# SnapItBreakoutRev1.net
KiCad netlist of a schematic drawn in Altium Designer
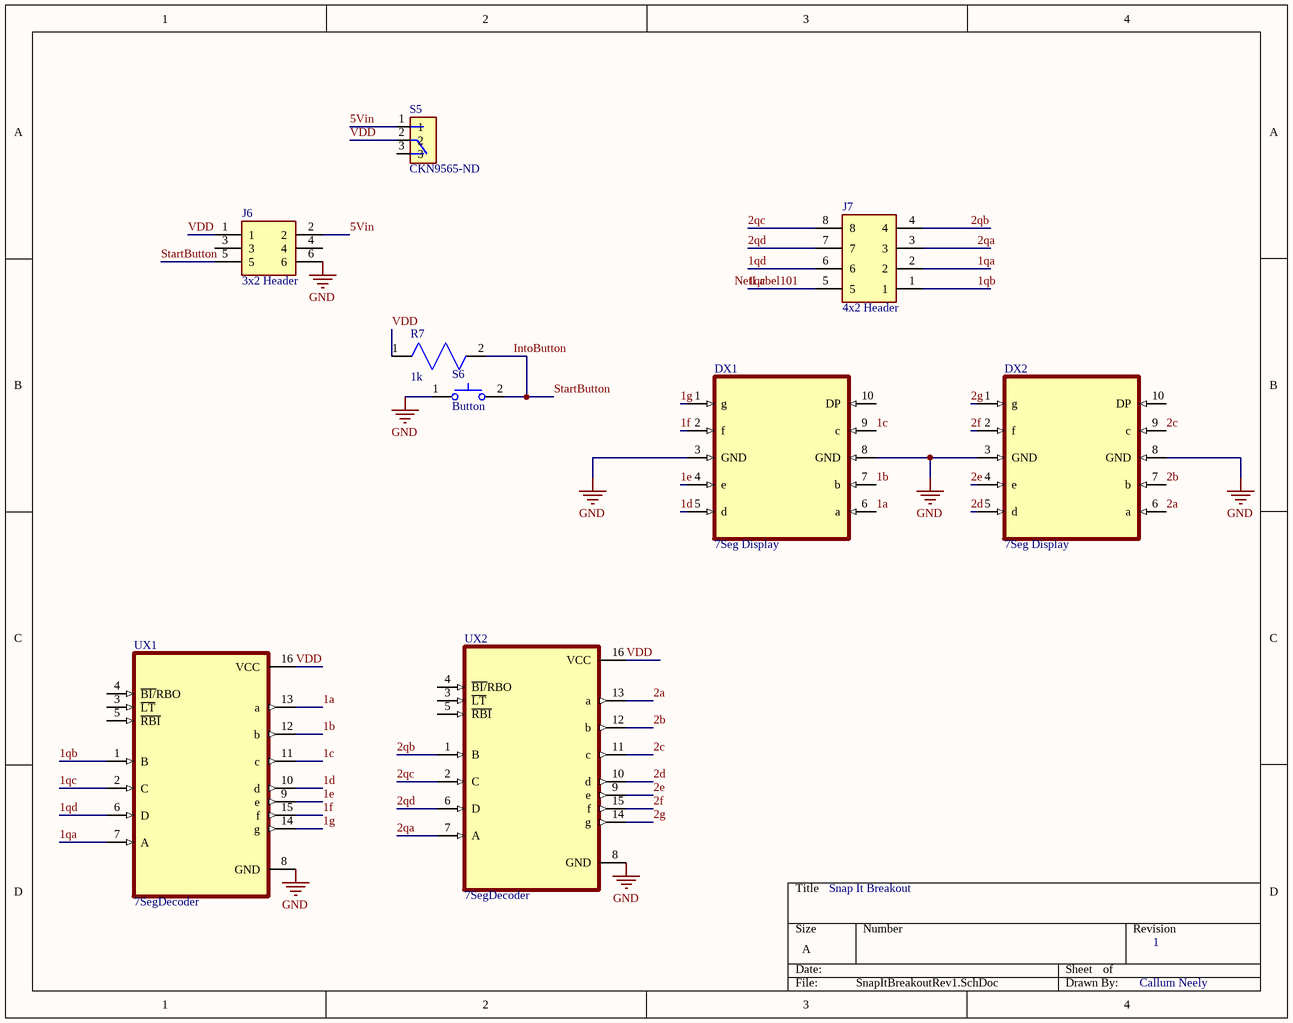
[diagram p0: SnapItBreakoutRev1.SchDoc]

(export (version "E")
  (design (tool "Eeschema 10.0.6"))
  (components
    (comp (ref "DX1")
      (value "7Seg Display")
      (footprint "7 Seg")
      (libsource (lib "JDLib") (part "7Seg Display"))
    )
    (comp (ref "DX2")
      (value "7Seg Display")
      (footprint "7 Seg")
      (libsource (lib "JDLib") (part "7Seg Display"))
    )
    (comp (ref "J6")
      (value "3x2 Header")
      (footprint "3x2 Header")
      (libsource (lib "JDLib") (part "3x2 Header"))
    )
    (comp (ref "J7")
      (value "4x2 Header")
      (footprint "4x2 Header")
      (libsource (lib "JDLib") (part "4x2 Header"))
    )
    (comp (ref "R7") (value "1k") (footprint "0402Basic") (libsource (lib "JDLib") (part "RES")))
    (comp (ref "S5")
      (value "CKN9565-ND")
      (footprint "Slide Switch")
      (libsource (lib "JDLib") (part "Switch"))
    )
    (comp (ref "S6") (value "Button") (footprint "Pushbutton") (libsource (lib "JDLib") (part "Button")))
    (comp (ref "UX1")
      (value "7SegDecoder")
      (footprint "DisplayDecoder")
      (libsource (lib "JDLib") (part "7SegDecoder"))
    )
    (comp (ref "UX2")
      (value "7SegDecoder")
      (footprint "DisplayDecoder")
      (libsource (lib "JDLib") (part "7SegDecoder"))
    )
  )
  (nets
    (net (code "1") (name "/1a") (class "Default")
      (node (ref "DX1") (pin "6") (pinfunction "a_6") (pintype "input"))
      (node (ref "UX1") (pin "13") (pinfunction "a_13") (pintype "output"))
    )
    (net (code "2") (name "/1b") (class "Default")
      (node (ref "DX1") (pin "7") (pinfunction "b_7") (pintype "input"))
      (node (ref "UX1") (pin "12") (pinfunction "b_12") (pintype "output"))
    )
    (net (code "3") (name "/1c") (class "Default")
      (node (ref "DX1") (pin "9") (pinfunction "c_9") (pintype "input"))
      (node (ref "UX1") (pin "11") (pinfunction "c_11") (pintype "output"))
    )
    (net (code "4") (name "/1d") (class "Default")
      (node (ref "DX1") (pin "5") (pinfunction "d_5") (pintype "input"))
      (node (ref "UX1") (pin "10") (pinfunction "d_10") (pintype "output"))
    )
    (net (code "5") (name "/1e") (class "Default")
      (node (ref "DX1") (pin "4") (pinfunction "e_4") (pintype "input"))
      (node (ref "UX1") (pin "9") (pinfunction "e_9") (pintype "output"))
    )
    (net (code "6") (name "/1f") (class "Default")
      (node (ref "DX1") (pin "2") (pinfunction "f_2") (pintype "input"))
      (node (ref "UX1") (pin "15") (pinfunction "f_15") (pintype "output"))
    )
    (net (code "7") (name "/1g") (class "Default")
      (node (ref "DX1") (pin "1") (pinfunction "g_1") (pintype "input"))
      (node (ref "UX1") (pin "14") (pinfunction "g_14") (pintype "output"))
    )
    (net (code "8") (name "/1qa") (class "Default")
      (node (ref "J7") (pin "2") (pinfunction "2_2") (pintype "passive"))
      (node (ref "UX1") (pin "7") (pinfunction "A_7") (pintype "input"))
    )
    (net (code "9") (name "/1qb") (class "Default")
      (node (ref "J7") (pin "1") (pinfunction "1_1") (pintype "passive"))
      (node (ref "UX1") (pin "1") (pinfunction "B_1") (pintype "input"))
    )
    (net (code "10") (name "/1qc") (class "Default")
      (node (ref "J7") (pin "5") (pinfunction "5_5") (pintype "passive"))
      (node (ref "UX1") (pin "2") (pinfunction "C_2") (pintype "input"))
    )
    (net (code "11") (name "/1qd") (class "Default")
      (node (ref "J7") (pin "6") (pinfunction "6_6") (pintype "passive"))
      (node (ref "UX1") (pin "6") (pinfunction "D_6") (pintype "input"))
    )
    (net (code "12") (name "/2a") (class "Default")
      (node (ref "DX2") (pin "6") (pinfunction "a_6") (pintype "input"))
      (node (ref "UX2") (pin "13") (pinfunction "a_13") (pintype "output"))
    )
    (net (code "13") (name "/2b") (class "Default")
      (node (ref "DX2") (pin "7") (pinfunction "b_7") (pintype "input"))
      (node (ref "UX2") (pin "12") (pinfunction "b_12") (pintype "output"))
    )
    (net (code "14") (name "/2c") (class "Default")
      (node (ref "DX2") (pin "9") (pinfunction "c_9") (pintype "input"))
      (node (ref "UX2") (pin "11") (pinfunction "c_11") (pintype "output"))
    )
    (net (code "15") (name "/2d") (class "Default")
      (node (ref "DX2") (pin "5") (pinfunction "d_5") (pintype "input"))
      (node (ref "UX2") (pin "10") (pinfunction "d_10") (pintype "output"))
    )
    (net (code "16") (name "/2e") (class "Default")
      (node (ref "DX2") (pin "4") (pinfunction "e_4") (pintype "input"))
      (node (ref "UX2") (pin "9") (pinfunction "e_9") (pintype "output"))
    )
    (net (code "17") (name "/2f") (class "Default")
      (node (ref "DX2") (pin "2") (pinfunction "f_2") (pintype "input"))
      (node (ref "UX2") (pin "15") (pinfunction "f_15") (pintype "output"))
    )
    (net (code "18") (name "/2g") (class "Default")
      (node (ref "DX2") (pin "1") (pinfunction "g_1") (pintype "input"))
      (node (ref "UX2") (pin "14") (pinfunction "g_14") (pintype "output"))
    )
    (net (code "19") (name "/2qa") (class "Default")
      (node (ref "J7") (pin "3") (pinfunction "3_3") (pintype "passive"))
      (node (ref "UX2") (pin "7") (pinfunction "A_7") (pintype "input"))
    )
    (net (code "20") (name "/2qb") (class "Default")
      (node (ref "J7") (pin "4") (pinfunction "4_4") (pintype "passive"))
      (node (ref "UX2") (pin "1") (pinfunction "B_1") (pintype "input"))
    )
    (net (code "21") (name "/2qc") (class "Default")
      (node (ref "J7") (pin "8") (pinfunction "8_8") (pintype "passive"))
      (node (ref "UX2") (pin "2") (pinfunction "C_2") (pintype "input"))
    )
    (net (code "22") (name "/2qd") (class "Default")
      (node (ref "J7") (pin "7") (pinfunction "7_7") (pintype "passive"))
      (node (ref "UX2") (pin "6") (pinfunction "D_6") (pintype "input"))
    )
    (net (code "23") (name "/5Vin") (class "Default")
      (node (ref "J6") (pin "2") (pinfunction "2_2") (pintype "passive"))
      (node (ref "S5") (pin "1") (pinfunction "1_1") (pintype "passive"))
    )
    (net (code "24") (name "/IntoButton") (class "Default")
      (node (ref "J6") (pin "5") (pinfunction "5_5") (pintype "passive"))
      (node (ref "R7") (pin "2") (pinfunction "=name_2") (pintype "passive"))
      (node (ref "S6") (pin "2") (pinfunction "=name_2") (pintype "passive"))
    )
    (net (code "26") (name "/VDD") (class "Default")
      (node (ref "J6") (pin "1") (pinfunction "1_1") (pintype "passive"))
      (node (ref "R7") (pin "1") (pinfunction "=name_1") (pintype "passive"))
      (node (ref "S5") (pin "2") (pinfunction "2_2") (pintype "passive"))
      (node (ref "UX1") (pin "16") (pinfunction "VCC_16") (pintype "power_in"))
      (node (ref "UX2") (pin "16") (pinfunction "VCC_16") (pintype "power_in"))
    )
    (net (code "27") (name "GND") (class "Default")
      (node (ref "DX1") (pin "3") (pinfunction "GND_3") (pintype "input"))
      (node (ref "DX1") (pin "8") (pinfunction "GND_8") (pintype "input"))
      (node (ref "DX2") (pin "3") (pinfunction "GND_3") (pintype "input"))
      (node (ref "DX2") (pin "8") (pinfunction "GND_8") (pintype "input"))
      (node (ref "J6") (pin "6") (pinfunction "6_6") (pintype "passive"))
      (node (ref "S6") (pin "1") (pinfunction "=name_1") (pintype "passive"))
      (node (ref "UX1") (pin "8") (pinfunction "GND_8") (pintype "power_in"))
      (node (ref "UX2") (pin "8") (pinfunction "GND_8") (pintype "power_in"))
    )
    (net (code "28") (name "unconnected-(DX1-DP-Pad10)") (class "Default")
      (node (ref "DX1") (pin "10") (pinfunction "DP_10") (pintype "input"))
    )
    (net (code "29") (name "unconnected-(DX2-DP-Pad10)") (class "Default")
      (node (ref "DX2") (pin "10") (pinfunction "DP_10") (pintype "input"))
    )
    (net (code "30") (name "unconnected-(J6-Pad3)") (class "Default")
      (node (ref "J6") (pin "3") (pinfunction "3_3") (pintype "passive"))
    )
    (net (code "31") (name "unconnected-(J6-Pad4)") (class "Default")
      (node (ref "J6") (pin "4") (pinfunction "4_4") (pintype "passive"))
    )
    (net (code "32") (name "unconnected-(S5-Pad3)") (class "Default")
      (node (ref "S5") (pin "3") (pinfunction "3_3") (pintype "passive"))
    )
    (net (code "33") (name "unconnected-(UX1-~{BI{slash}}RBO-Pad4)") (class "Default")
      (node (ref "UX1") (pin "4") (pinfunction "~{BI/}RBO_4") (pintype "input"))
    )
    (net (code "34") (name "unconnected-(UX1-~{LT}-Pad3)") (class "Default")
      (node (ref "UX1") (pin "3") (pinfunction "~{LT}_3") (pintype "input"))
    )
    (net (code "35") (name "unconnected-(UX1-~{RBI}-Pad5)") (class "Default")
      (node (ref "UX1") (pin "5") (pinfunction "~{RBI}_5") (pintype "input"))
    )
    (net (code "36") (name "unconnected-(UX2-~{BI{slash}}RBO-Pad4)") (class "Default")
      (node (ref "UX2") (pin "4") (pinfunction "~{BI/}RBO_4") (pintype "input"))
    )
    (net (code "37") (name "unconnected-(UX2-~{LT}-Pad3)") (class "Default")
      (node (ref "UX2") (pin "3") (pinfunction "~{LT}_3") (pintype "input"))
    )
    (net (code "38") (name "unconnected-(UX2-~{RBI}-Pad5)") (class "Default")
      (node (ref "UX2") (pin "5") (pinfunction "~{RBI}_5") (pintype "input"))
    )
  )
)
